# Output_Terminals.net
KiCad netlist of a schematic drawn in Altium Designer
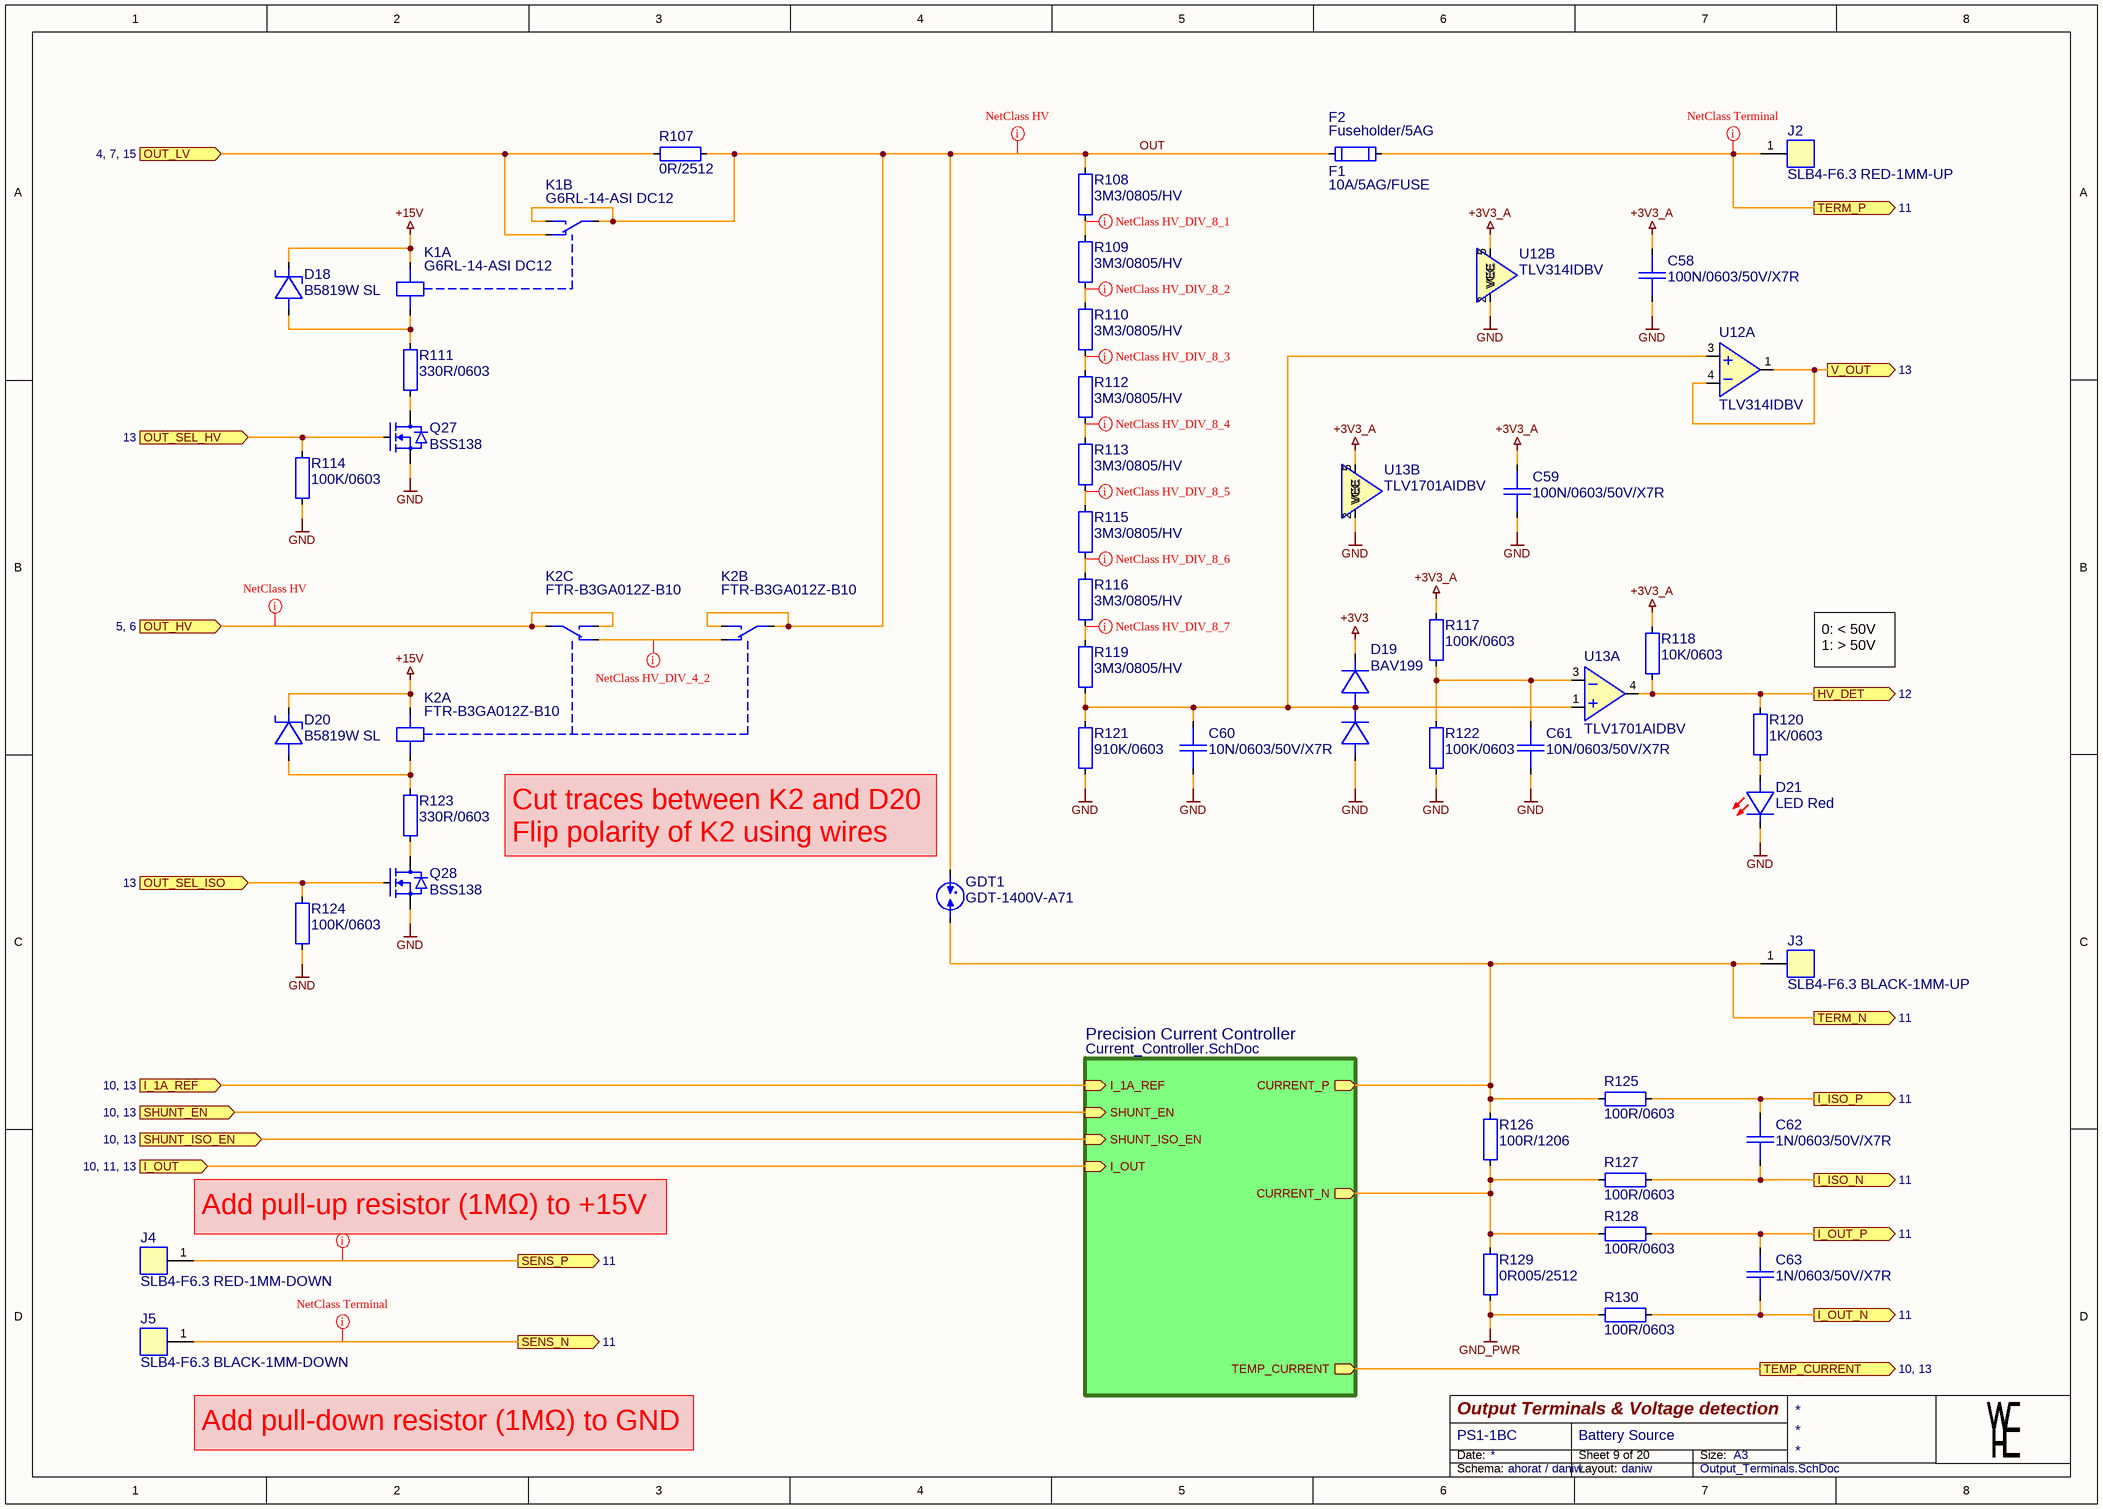
[diagram p0: Output_Terminals.SchDoc]

(export (version "E")
  (design (tool "Eeschema 10.0.6"))
  (components
    (comp (ref "C58")
      (value "100N/0603/50V/X7R")
      (footprint "CAP0603_X7R")
      (description "CAP SM 0603 100nF 50V X7R")
      (fields (field (name "MANUFACTURER") "GENERIC"))
      (libsource (lib "daniw_altium_lib") (part "C"))
    )
    (comp (ref "C59")
      (value "100N/0603/50V/X7R")
      (footprint "CAP0603_X7R")
      (description "CAP SM 0603 100nF 50V X7R")
      (fields (field (name "MANUFACTURER") "GENERIC"))
      (libsource (lib "daniw_altium_lib") (part "C"))
    )
    (comp (ref "C60")
      (value "10N/0603/50V/X7R")
      (footprint "CAP0603_X7R")
      (description "CAP SM 0603 10nF 50V X7R")
      (fields (field (name "MANUFACTURER") "GENERIC"))
      (libsource (lib "daniw_altium_lib") (part "C"))
    )
    (comp (ref "C61")
      (value "10N/0603/50V/X7R")
      (footprint "CAP0603_X7R")
      (description "CAP SM 0603 10nF 50V X7R")
      (fields (field (name "MANUFACTURER") "GENERIC"))
      (libsource (lib "daniw_altium_lib") (part "C"))
    )
    (comp (ref "C62")
      (value "1N/0603/50V/X7R")
      (footprint "CAP0603_X7R")
      (description "CAP SM 0603 1.0nF 50V X7R")
      (fields (field (name "MANUFACTURER") "GENERIC"))
      (libsource (lib "daniw_altium_lib") (part "C"))
    )
    (comp (ref "C63")
      (value "1N/0603/50V/X7R")
      (footprint "CAP0603_X7R")
      (description "CAP SM 0603 1.0nF 50V X7R")
      (fields (field (name "MANUFACTURER") "GENERIC"))
      (libsource (lib "daniw_altium_lib") (part "C"))
    )
    (comp (ref "D18")
      (value "B5819W SL")
      (footprint "SOD3718X125")
      (description "40V 600mV@1A 1A SOD-123 Schottky Barrier Diodes")
      (fields (field (name "MANUFACTURER") "GENERIC"))
      (libsource (lib "daniw_altium_lib") (part "D_Schottky"))
    )
    (comp (ref "D19")
      (value "BAV199")
      (footprint "SOT2395P280X125-3-SE")
      (description "Silicon Low Leakage Diode 85V")
      (fields (field (name "MANUFACTURER") "Infineon Technologies"))
      (libsource (lib "daniw_altium_lib") (part "D_Serie"))
    )
    (comp (ref "D20")
      (value "B5819W SL")
      (footprint "SOD3718X125")
      (description "40V 600mV@1A 1A SOD-123 Schottky Barrier Diodes")
      (fields (field (name "MANUFACTURER") "GENERIC"))
      (libsource (lib "daniw_altium_lib") (part "D_Schottky"))
    )
    (comp (ref "D21")
      (value "LED Red")
      (footprint "LED0805_RED")
      (description "Generic LED Red 0805")
      (fields (field (name "PART NUMBER") "LED Red 0805") (field (name "MANUFACTURER") "GENERIC"))
      (libsource (lib "daniw_altium_lib") (part "LED_RED"))
    )
    (comp (ref "F1")
      (value "10A/5AG/FUSE")
      (footprint "Fuse_5AG_5mm")
      (description "Fuse 1000V AC/DC 10A 5AG 10.3x38mm")
      (fields (field (name "MANUFACTURER") "Phoenix Contact"))
      (libsource (lib "daniw_altium_lib") (part "Fuse_Nolead"))
    )
    (comp (ref "F2")
      (value "Fuseholder/5AG")
      (footprint "KEYSTONE_3576")
      (libsource (lib "daniw_altium_lib") (part "Fuse_Holder"))
    )
    (comp (ref "GDT1")
      (value "GDT-1400V-A71")
      (footprint "GDTAD1200W100L800D800H1200")
      (description "2-electrode surge arrester, 1400V, 10kA, A71 series, 12mm lead spacing, 4mm standoff height")
      (fields (field (name "PART NUMBER") "GDT-1400V-A71-12MM-4MM") (field (name "MANUFACTURER") "TDK"))
      (libsource (lib "daniw_altium_lib") (part "GDT_2"))
    )
    (comp (ref "J2")
      (value "SLB4-F6.3 RED-1MM-UP")
      (footprint "SLB4-F6.3-RED")
      (fields (field (name "MANUFACTURER") "Stäubli"))
      (libsource (lib "") (part "CON1_1"))
    )
    (comp (ref "J3")
      (value "SLB4-F6.3 BLACK-1MM-UP")
      (footprint "SLB4-F6.3-BLACK")
      (fields (field (name "MANUFACTURER") "Stäubli"))
      (libsource (lib "") (part "CON1_1"))
    )
    (comp (ref "J4")
      (value "SLB4-F6.3 RED-1MM-DOWN")
      (footprint "SLB4-F6.3-RED")
      (fields (field (name "MANUFACTURER") "Stäubli"))
      (libsource (lib "daniw_altium_lib") (part "CON1"))
    )
    (comp (ref "J5")
      (value "SLB4-F6.3 BLACK-1MM-DOWN")
      (footprint "SLB4-F6.3-BLACK")
      (fields (field (name "MANUFACTURER") "Stäubli"))
      (libsource (lib "daniw_altium_lib") (part "CON1"))
    )
    (comp (ref "K1")
      (value "G6RL-14-ASI DC12")
      (footprint "G6RL-1")
      (description "RELAY GEN PURPOSE SPDT 8A 12V")
      (fields (field (name "MANUFACTURER") "Omron Electronics Inc-EMC Div"))
      (libsource (lib "daniw_altium_lib") (part "REL_SPDT"))
    )
    (comp (ref "K2")
      (value "FTR-B3GA012Z-B10")
      (footprint "FTR-B3G")
      (description "FTR-B3 Series Ultra Miniature Relay 2 Poles - 2 A (Low Profile Signal Relay)")
      (fields (field (name "MANUFACTURER") "Fujitsu"))
      (libsource (lib "daniw_altium_lib") (part "REL_DPDT"))
    )
    (comp (ref "Q27")
      (value "BSS138")
      (footprint "SOT2395P280X125-3-SE")
      (description "N-Kanal 50 V 220mA (Ta) 350mW (Ta) Oberflächenmontage SOT-23")
      (fields (field (name "MANUFACTURER") "GENERIC"))
      (libsource (lib "daniw_altium_lib") (part "MOSFET_N_G1_D3_S2"))
    )
    (comp (ref "Q28")
      (value "BSS138")
      (footprint "SOT2395P280X125-3-SE")
      (description "N-Kanal 50 V 220mA (Ta) 350mW (Ta) Oberflächenmontage SOT-23")
      (fields (field (name "MANUFACTURER") "GENERIC"))
      (libsource (lib "daniw_altium_lib") (part "MOSFET_N_G1_D3_S2"))
    )
    (comp (ref "R107")
      (value "0R/2512")
      (footprint "R2512-0.65-WW")
      (description "RES SM 2512 0R")
      (fields (field (name "MANUFACTURER") "GENERIC"))
      (libsource (lib "daniw_altium_lib") (part "R"))
    )
    (comp (ref "R108")
      (value "3M3/0805/HV")
      (footprint "R0805-0.50-HV-WW")
      (description "RES SM 0805 3M3 High voltage")
      (fields (field (name "MANUFACTURER") "GENERIC"))
      (libsource (lib "daniw_altium_lib") (part "R"))
    )
    (comp (ref "R109")
      (value "3M3/0805/HV")
      (footprint "R0805-0.50-HV-WW")
      (description "RES SM 0805 3M3 High voltage")
      (fields (field (name "MANUFACTURER") "GENERIC"))
      (libsource (lib "daniw_altium_lib") (part "R"))
    )
    (comp (ref "R110")
      (value "3M3/0805/HV")
      (footprint "R0805-0.50-HV-WW")
      (description "RES SM 0805 3M3 High voltage")
      (fields (field (name "MANUFACTURER") "GENERIC"))
      (libsource (lib "daniw_altium_lib") (part "R"))
    )
    (comp (ref "R111")
      (value "330R/0603")
      (footprint "R0603-0.40-WW")
      (description "RES SM 0603 330R")
      (fields (field (name "MANUFACTURER") "GENERIC"))
      (libsource (lib "daniw_altium_lib") (part "R"))
    )
    (comp (ref "R112")
      (value "3M3/0805/HV")
      (footprint "R0805-0.50-HV-WW")
      (description "RES SM 0805 3M3 High voltage")
      (fields (field (name "MANUFACTURER") "GENERIC"))
      (libsource (lib "daniw_altium_lib") (part "R"))
    )
    (comp (ref "R113")
      (value "3M3/0805/HV")
      (footprint "R0805-0.50-HV-WW")
      (description "RES SM 0805 3M3 High voltage")
      (fields (field (name "MANUFACTURER") "GENERIC"))
      (libsource (lib "daniw_altium_lib") (part "R"))
    )
    (comp (ref "R114")
      (value "100K/0603")
      (footprint "R0603-0.40-WW")
      (description "RES SM 0603 100K")
      (fields (field (name "MANUFACTURER") "GENERIC"))
      (libsource (lib "daniw_altium_lib") (part "R"))
    )
    (comp (ref "R115")
      (value "3M3/0805/HV")
      (footprint "R0805-0.50-HV-WW")
      (description "RES SM 0805 3M3 High voltage")
      (fields (field (name "MANUFACTURER") "GENERIC"))
      (libsource (lib "daniw_altium_lib") (part "R"))
    )
    (comp (ref "R116")
      (value "3M3/0805/HV")
      (footprint "R0805-0.50-HV-WW")
      (description "RES SM 0805 3M3 High voltage")
      (fields (field (name "MANUFACTURER") "GENERIC"))
      (libsource (lib "daniw_altium_lib") (part "R"))
    )
    (comp (ref "R117")
      (value "100K/0603")
      (footprint "R0603-0.40-WW")
      (description "RES SM 0603 100K")
      (fields (field (name "MANUFACTURER") "GENERIC"))
      (libsource (lib "daniw_altium_lib") (part "R"))
    )
    (comp (ref "R118")
      (value "10K/0603")
      (footprint "R0603-0.40-WW")
      (description "RES SM 0603 10K")
      (fields (field (name "MANUFACTURER") "GENERIC"))
      (libsource (lib "daniw_altium_lib") (part "R"))
    )
    (comp (ref "R119")
      (value "3M3/0805/HV")
      (footprint "R0805-0.50-HV-WW")
      (description "RES SM 0805 3M3 High voltage")
      (fields (field (name "MANUFACTURER") "GENERIC"))
      (libsource (lib "daniw_altium_lib") (part "R"))
    )
    (comp (ref "R120")
      (value "1K/0603")
      (footprint "R0603-0.40-WW")
      (description "RES SM 0603 1K")
      (fields (field (name "MANUFACTURER") "GENERIC"))
      (libsource (lib "daniw_altium_lib") (part "R"))
    )
    (comp (ref "R121")
      (value "910K/0603")
      (footprint "R0603-0.40-WW")
      (description "RES SM 0603 910K")
      (fields (field (name "MANUFACTURER") "GENERIC"))
      (libsource (lib "daniw_altium_lib") (part "R"))
    )
    (comp (ref "R122")
      (value "100K/0603")
      (footprint "R0603-0.40-WW")
      (description "RES SM 0603 100K")
      (fields (field (name "MANUFACTURER") "GENERIC"))
      (libsource (lib "daniw_altium_lib") (part "R"))
    )
    (comp (ref "R123")
      (value "330R/0603")
      (footprint "R0603-0.40-WW")
      (description "RES SM 0603 330R")
      (fields (field (name "MANUFACTURER") "GENERIC"))
      (libsource (lib "daniw_altium_lib") (part "R"))
    )
    (comp (ref "R124")
      (value "100K/0603")
      (footprint "R0603-0.40-WW")
      (description "RES SM 0603 100K")
      (fields (field (name "MANUFACTURER") "GENERIC"))
      (libsource (lib "daniw_altium_lib") (part "R"))
    )
    (comp (ref "R125")
      (value "100R/0603")
      (footprint "R0603-0.40-WW")
      (description "RES SM 0603 100R")
      (fields (field (name "MANUFACTURER") "GENERIC"))
      (libsource (lib "daniw_altium_lib") (part "R"))
    )
    (comp (ref "R126")
      (value "100R/1206")
      (footprint "R1206-0.80-WW")
      (description "RES SM 1206 100R")
      (fields (field (name "MANUFACTURER") "GENERIC"))
      (libsource (lib "daniw_altium_lib") (part "R"))
    )
    (comp (ref "R127")
      (value "100R/0603")
      (footprint "R0603-0.40-WW")
      (description "RES SM 0603 100R")
      (fields (field (name "MANUFACTURER") "GENERIC"))
      (libsource (lib "daniw_altium_lib") (part "R"))
    )
    (comp (ref "R128")
      (value "100R/0603")
      (footprint "R0603-0.40-WW")
      (description "RES SM 0603 100R")
      (fields (field (name "MANUFACTURER") "GENERIC"))
      (libsource (lib "daniw_altium_lib") (part "R"))
    )
    (comp (ref "R129")
      (value "0R005/2512")
      (footprint "R2512-0.65-WW")
      (description "RES SM 2512 0R005")
      (fields (field (name "MANUFACTURER") "GENERIC"))
      (libsource (lib "daniw_altium_lib") (part "R"))
    )
    (comp (ref "R130")
      (value "100R/0603")
      (footprint "R0603-0.40-WW")
      (description "RES SM 0603 100R")
      (fields (field (name "MANUFACTURER") "GENERIC"))
      (libsource (lib "daniw_altium_lib") (part "R"))
    )
    (comp (ref "U12")
      (value "TLV314IDBV")
      (footprint "SOT2395P280X125-5-NW")
      (description "TLV314, 3-MHz, Low-Power, Internal EMI Filter, RRIO, Operational Amplifier")
      (fields (field (name "PART NUMBER") "TLV314 SOT23") (field (name "MANUFACTURER") "Texas Instruments"))
      (libsource (lib "daniw_altium_lib") (part "OPA_O1_P3_N4_VCC5_VEE2"))
    )
    (comp (ref "U13")
      (value "TLV1701AIDBV")
      (footprint "SOT2395P280X125-5-NW")
      (description "TLV1701 2.2-V to 36-V, microPower Comparato")
      (fields (field (name "PART NUMBER") "TLV1701 SOT23") (field (name "MANUFACTURER") "Texas Instruments"))
      (libsource (lib "daniw_altium_lib") (part "OPA_O4_P1_N3_VCC5_VEE2"))
    )
  )
  (nets
    (net (code "1") (name "+3V3") (class "Default")
      (node (ref "D19") (pin "2") (pinfunction "K2_2") (pintype "passive"))
    )
    (net (code "2") (name "+3V3_A") (class "Default")
      (node (ref "C58") (pin "1") (pinfunction "1_1") (pintype "passive"))
      (node (ref "C59") (pin "1") (pinfunction "1_1") (pintype "passive"))
      (node (ref "R117") (pin "1") (pinfunction "1_1") (pintype "passive"))
      (node (ref "R118") (pin "1") (pinfunction "1_1") (pintype "passive"))
      (node (ref "U12") (pin "5") (pinfunction "VCC_5") (pintype "passive"))
      (node (ref "U13") (pin "5") (pinfunction "VCC_5") (pintype "passive"))
    )
    (net (code "3") (name "+15V") (class "Default")
      (node (ref "D18") (pin "1") (pinfunction "C_1") (pintype "passive"))
      (node (ref "D20") (pin "1") (pinfunction "C_1") (pintype "passive"))
      (node (ref "K1") (pin "2") (pinfunction "2_2") (pintype "passive"))
      (node (ref "K2") (pin "2") (pinfunction "2_2") (pintype "passive"))
    )
    (net (code "4") (name "/CURRENT_N") (class "Default")
      (node (ref "R126") (pin "2") (pinfunction "2_2") (pintype "passive"))
      (node (ref "R127") (pin "1") (pinfunction "1_1") (pintype "passive"))
      (node (ref "R128") (pin "1") (pinfunction "1_1") (pintype "passive"))
      (node (ref "R129") (pin "1") (pinfunction "1_1") (pintype "passive"))
    )
    (net (code "5") (name "/HV_DET") (class "Default")
      (node (ref "R118") (pin "2") (pinfunction "2_2") (pintype "passive"))
      (node (ref "R120") (pin "2") (pinfunction "2_2") (pintype "passive"))
      (node (ref "U13") (pin "4") (pinfunction "OUT_4") (pintype "passive"))
    )
    (net (code "7") (name "/I_ISO_N") (class "Default")
      (node (ref "C62") (pin "2") (pinfunction "2_2") (pintype "passive"))
      (node (ref "R127") (pin "2") (pinfunction "2_2") (pintype "passive"))
    )
    (net (code "8") (name "/I_ISO_P") (class "Default")
      (node (ref "C62") (pin "1") (pinfunction "1_1") (pintype "passive"))
      (node (ref "R125") (pin "2") (pinfunction "2_2") (pintype "passive"))
    )
    (net (code "10") (name "/I_OUT_N") (class "Default")
      (node (ref "C63") (pin "2") (pinfunction "2_2") (pintype "passive"))
      (node (ref "R130") (pin "2") (pinfunction "2_2") (pintype "passive"))
    )
    (net (code "11") (name "/I_OUT_P") (class "Default")
      (node (ref "C63") (pin "1") (pinfunction "1_1") (pintype "passive"))
      (node (ref "R128") (pin "2") (pinfunction "2_2") (pintype "passive"))
    )
    (net (code "12") (name "/OUT") (class "Default")
      (node (ref "F2") (pin "1") (pinfunction "1_1") (pintype "passive"))
      (node (ref "GDT1") (pin "1") (pinfunction "1_1") (pintype "passive"))
      (node (ref "K1") (pin "3") (pinfunction "COM1_3") (pintype "passive"))
      (node (ref "K1") (pin "5") (pinfunction "NO1_5") (pintype "passive"))
      (node (ref "K2") (pin "3") (pinfunction "COM1_3") (pintype "passive"))
      (node (ref "K2") (pin "5") (pinfunction "NO1_5") (pintype "passive"))
      (node (ref "R107") (pin "1") (pinfunction "1_1") (pintype "passive"))
      (node (ref "R108") (pin "1") (pinfunction "1_1") (pintype "passive"))
    )
    (net (code "13") (name "/OUT_HV") (class "Default")
      (node (ref "K2") (pin "6") (pinfunction "COM2_6") (pintype "passive"))
      (node (ref "K2") (pin "8") (pinfunction "NO2_8") (pintype "passive"))
    )
    (net (code "14") (name "/OUT_LV") (class "Default")
      (node (ref "K1") (pin "4") (pinfunction "NC1_4") (pintype "passive"))
      (node (ref "R107") (pin "2") (pinfunction "2_2") (pintype "passive"))
    )
    (net (code "15") (name "/OUT_SEL_HV") (class "Default")
      (node (ref "Q27") (pin "1") (pinfunction "GATE_1") (pintype "passive"))
      (node (ref "R114") (pin "1") (pinfunction "1_1") (pintype "passive"))
    )
    (net (code "16") (name "/OUT_SEL_ISO") (class "Default")
      (node (ref "Q28") (pin "1") (pinfunction "GATE_1") (pintype "passive"))
      (node (ref "R124") (pin "1") (pinfunction "1_1") (pintype "passive"))
    )
    (net (code "17") (name "/SENS_N") (class "Default") (node (ref "J5") (pin "1") (pintype "passive")))
    (net (code "18") (name "/SENS_P") (class "Default") (node (ref "J4") (pin "1") (pintype "passive")))
    (net (code "22") (name "/TERM_N") (class "Default")
      (node (ref "GDT1") (pin "2") (pinfunction "2_2") (pintype "passive"))
      (node (ref "J3") (pin "1") (pintype "passive"))
      (node (ref "R125") (pin "1") (pinfunction "1_1") (pintype "passive"))
      (node (ref "R126") (pin "1") (pinfunction "1_1") (pintype "passive"))
    )
    (net (code "23") (name "/TERM_P") (class "Default")
      (node (ref "F2") (pin "2") (pinfunction "2_2") (pintype "passive"))
      (node (ref "J2") (pin "1") (pintype "passive"))
    )
    (net (code "24") (name "/V_OUT") (class "Default")
      (node (ref "U12") (pin "1") (pinfunction "OUT_1") (pintype "passive"))
      (node (ref "U12") (pin "4") (pinfunction "IN-_4") (pintype "passive"))
    )
    (net (code "25") (name "GND") (class "Default")
      (node (ref "C58") (pin "2") (pinfunction "2_2") (pintype "passive"))
      (node (ref "C59") (pin "2") (pinfunction "2_2") (pintype "passive"))
      (node (ref "C60") (pin "2") (pinfunction "2_2") (pintype "passive"))
      (node (ref "C61") (pin "2") (pinfunction "2_2") (pintype "passive"))
      (node (ref "D19") (pin "1") (pinfunction "A1_1") (pintype "passive"))
      (node (ref "D21") (pin "1") (pinfunction "C_1") (pintype "passive"))
      (node (ref "Q27") (pin "2") (pinfunction "SOURCE_2") (pintype "passive"))
      (node (ref "Q28") (pin "2") (pinfunction "SOURCE_2") (pintype "passive"))
      (node (ref "R114") (pin "2") (pinfunction "2_2") (pintype "passive"))
      (node (ref "R121") (pin "2") (pinfunction "2_2") (pintype "passive"))
      (node (ref "R122") (pin "2") (pinfunction "2_2") (pintype "passive"))
      (node (ref "R124") (pin "2") (pinfunction "2_2") (pintype "passive"))
      (node (ref "U12") (pin "2") (pinfunction "VEE_2") (pintype "passive"))
      (node (ref "U13") (pin "2") (pinfunction "VEE_2") (pintype "passive"))
    )
    (net (code "26") (name "GND_PWR") (class "Default")
      (node (ref "R129") (pin "2") (pinfunction "2_2") (pintype "passive"))
      (node (ref "R130") (pin "1") (pinfunction "1_1") (pintype "passive"))
    )
    (net (code "27") (name "Net-(D18-A)") (class "Default")
      (node (ref "D18") (pin "2") (pinfunction "A_2") (pintype "passive"))
      (node (ref "K1") (pin "1") (pinfunction "1_1") (pintype "passive"))
      (node (ref "R111") (pin "1") (pinfunction "1_1") (pintype "passive"))
    )
    (net (code "28") (name "Net-(D19-K1{slash}A2)") (class "Default")
      (node (ref "C60") (pin "1") (pinfunction "1_1") (pintype "passive"))
      (node (ref "D19") (pin "3") (pinfunction "K1/A2_3") (pintype "passive"))
      (node (ref "R119") (pin "2") (pinfunction "2_2") (pintype "passive"))
      (node (ref "R121") (pin "1") (pinfunction "1_1") (pintype "passive"))
      (node (ref "U12") (pin "3") (pinfunction "IN+_3") (pintype "passive"))
      (node (ref "U13") (pin "1") (pinfunction "IN+_1") (pintype "passive"))
    )
    (net (code "29") (name "Net-(D20-A)") (class "Default")
      (node (ref "D20") (pin "2") (pinfunction "A_2") (pintype "passive"))
      (node (ref "K2") (pin "1") (pinfunction "1_1") (pintype "passive"))
      (node (ref "R123") (pin "1") (pinfunction "1_1") (pintype "passive"))
    )
    (net (code "30") (name "Net-(D21-A)") (class "Default")
      (node (ref "D21") (pin "2") (pinfunction "A_2") (pintype "passive"))
      (node (ref "R120") (pin "1") (pinfunction "1_1") (pintype "passive"))
    )
    (net (code "31") (name "Net-(K2B-NC1)") (class "Default")
      (node (ref "K2") (pin "4") (pinfunction "NC1_4") (pintype "passive"))
      (node (ref "K2") (pin "7") (pinfunction "NC2_7") (pintype "passive"))
    )
    (net (code "32") (name "Net-(Q27-DRAIN)") (class "Default")
      (node (ref "Q27") (pin "3") (pinfunction "DRAIN_3") (pintype "passive"))
      (node (ref "R111") (pin "2") (pinfunction "2_2") (pintype "passive"))
    )
    (net (code "33") (name "Net-(Q28-DRAIN)") (class "Default")
      (node (ref "Q28") (pin "3") (pinfunction "DRAIN_3") (pintype "passive"))
      (node (ref "R123") (pin "2") (pinfunction "2_2") (pintype "passive"))
    )
    (net (code "34") (name "Net-(R108-Pad2)") (class "Default")
      (node (ref "R108") (pin "2") (pinfunction "2_2") (pintype "passive"))
      (node (ref "R109") (pin "1") (pinfunction "1_1") (pintype "passive"))
    )
    (net (code "35") (name "Net-(R109-Pad2)") (class "Default")
      (node (ref "R109") (pin "2") (pinfunction "2_2") (pintype "passive"))
      (node (ref "R110") (pin "1") (pinfunction "1_1") (pintype "passive"))
    )
    (net (code "36") (name "Net-(R110-Pad2)") (class "Default")
      (node (ref "R110") (pin "2") (pinfunction "2_2") (pintype "passive"))
      (node (ref "R112") (pin "1") (pinfunction "1_1") (pintype "passive"))
    )
    (net (code "37") (name "Net-(R112-Pad2)") (class "Default")
      (node (ref "R112") (pin "2") (pinfunction "2_2") (pintype "passive"))
      (node (ref "R113") (pin "1") (pinfunction "1_1") (pintype "passive"))
    )
    (net (code "38") (name "Net-(R113-Pad2)") (class "Default")
      (node (ref "R113") (pin "2") (pinfunction "2_2") (pintype "passive"))
      (node (ref "R115") (pin "1") (pinfunction "1_1") (pintype "passive"))
    )
    (net (code "39") (name "Net-(R115-Pad2)") (class "Default")
      (node (ref "R115") (pin "2") (pinfunction "2_2") (pintype "passive"))
      (node (ref "R116") (pin "1") (pinfunction "1_1") (pintype "passive"))
    )
    (net (code "40") (name "Net-(R116-Pad2)") (class "Default")
      (node (ref "R116") (pin "2") (pinfunction "2_2") (pintype "passive"))
      (node (ref "R119") (pin "1") (pinfunction "1_1") (pintype "passive"))
    )
    (net (code "41") (name "Net-(U13A-IN-)") (class "Default")
      (node (ref "C61") (pin "1") (pinfunction "1_1") (pintype "passive"))
      (node (ref "R117") (pin "2") (pinfunction "2_2") (pintype "passive"))
      (node (ref "R122") (pin "1") (pinfunction "1_1") (pintype "passive"))
      (node (ref "U13") (pin "3") (pinfunction "IN-_3") (pintype "passive"))
    )
  )
)
